# schematic.net
KiCad netlist of a schematic drawn in EAGLE
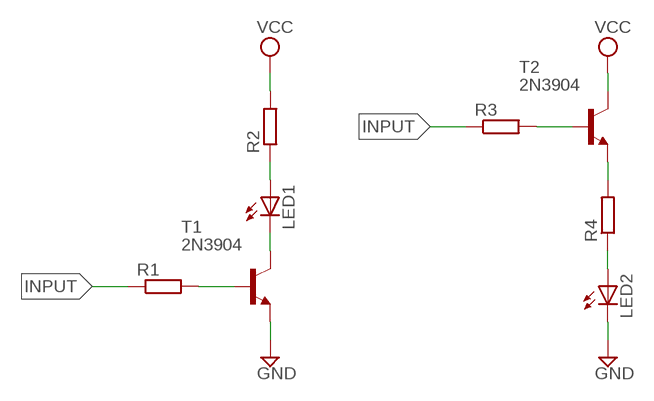
[diagram p0: schematic, sheet 1]

(export (version "E")
  (design (tool "Eeschema 10.0.6"))
  (components
    (comp (ref "LED1")
      (value "LED5MM")
      (footprint "eagle-import:LED5MM")
      (libsource (lib "eagle-import") (part "LED5MM"))
    )
    (comp (ref "LED2")
      (value "LED5MM")
      (footprint "eagle-import:LED5MM")
      (libsource (lib "eagle-import") (part "LED5MM"))
    )
    (comp (ref "R1")
      (value "R0204/7")
      (footprint "eagle-import:0204_7")
      (libsource (lib "eagle-import") (part "R0204/7"))
    )
    (comp (ref "R2")
      (value "R0204/7")
      (footprint "eagle-import:0204_7")
      (libsource (lib "eagle-import") (part "R0204/7"))
    )
    (comp (ref "R3")
      (value "R0204/7")
      (footprint "eagle-import:0204_7")
      (libsource (lib "eagle-import") (part "R0204/7"))
    )
    (comp (ref "R4")
      (value "R0204/7")
      (footprint "eagle-import:0204_7")
      (libsource (lib "eagle-import") (part "R0204/7"))
    )
    (comp (ref "T1")
      (value "2N3904")
      (footprint "eagle-import:TO92")
      (libsource (lib "eagle-import") (part "2N3904"))
    )
    (comp (ref "T2")
      (value "2N3904")
      (footprint "eagle-import:TO92")
      (libsource (lib "eagle-import") (part "2N3904"))
    )
  )
  (nets
    (net (code "1") (name "GND") (class "Default")
      (node (ref "LED2") (pin "K") (pinfunction "C_K") (pintype "passive"))
      (node (ref "T1") (pin "3") (pinfunction "E_3") (pintype "passive"))
    )
    (net (code "2") (name "INPUT") (class "Default")
      (node (ref "R1") (pin "1") (pinfunction "1_1") (pintype "passive"))
      (node (ref "R3") (pin "1") (pinfunction "1_1") (pintype "passive"))
    )
    (net (code "3") (name "Net-(LED1-C)") (class "Default")
      (node (ref "LED1") (pin "K") (pinfunction "C_K") (pintype "passive"))
      (node (ref "T1") (pin "1") (pinfunction "C_1") (pintype "passive"))
    )
    (net (code "4") (name "Net-(LED1-PadA)") (class "Default")
      (node (ref "LED1") (pin "A") (pinfunction "A_A") (pintype "passive"))
      (node (ref "R2") (pin "1") (pinfunction "1_1") (pintype "passive"))
    )
    (net (code "5") (name "Net-(LED2-PadA)") (class "Default")
      (node (ref "LED2") (pin "A") (pinfunction "A_A") (pintype "passive"))
      (node (ref "R4") (pin "1") (pinfunction "1_1") (pintype "passive"))
    )
    (net (code "6") (name "Net-(T1-B)") (class "Default")
      (node (ref "R1") (pin "2") (pinfunction "2_2") (pintype "passive"))
      (node (ref "T1") (pin "2") (pinfunction "B_2") (pintype "passive"))
    )
    (net (code "7") (name "Net-(T2-B)") (class "Default")
      (node (ref "R3") (pin "2") (pinfunction "2_2") (pintype "passive"))
      (node (ref "T2") (pin "2") (pinfunction "B_2") (pintype "passive"))
    )
    (net (code "8") (name "Net-(T2-E)") (class "Default")
      (node (ref "R4") (pin "2") (pinfunction "2_2") (pintype "passive"))
      (node (ref "T2") (pin "3") (pinfunction "E_3") (pintype "passive"))
    )
    (net (code "9") (name "VCC") (class "Default")
      (node (ref "R2") (pin "2") (pinfunction "2_2") (pintype "passive"))
      (node (ref "T2") (pin "1") (pinfunction "C_1") (pintype "passive"))
    )
  )
)
